# iotchair_uno-shield.net
KiCad netlist of a schematic drawn in EAGLE
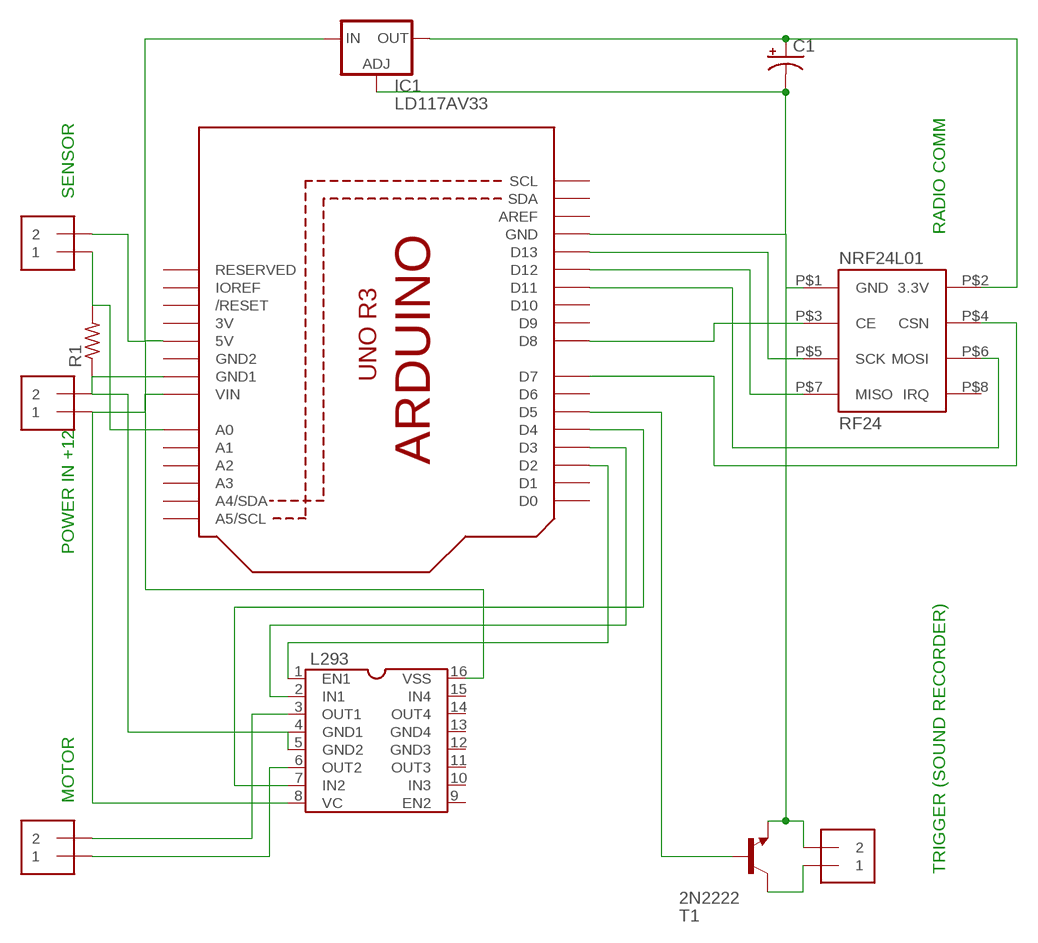
[diagram p0: schematic, sheet 1]

(export (version "E")
  (design (tool "Eeschema 10.0.6"))
  (components
    (comp (ref "+12V")
      (value "1X2-3.5MM")
      (footprint "eagle-import:1X2-3.5MM")
      (libsource (lib "eagle-import") (part "1X2-3.5MM"))
    )
    (comp (ref "A_SENS")
      (value "1X2-3.5MM")
      (footprint "eagle-import:1X2-3.5MM")
      (libsource (lib "eagle-import") (part "1X2-3.5MM"))
    )
    (comp (ref "C1")
      (value "CPOL-USE2-5")
      (footprint "eagle-import:E2-5")
      (libsource (lib "eagle-import") (part "CPOL-USE2-5"))
    )
    (comp (ref "IC1")
      (value "LD117AV33")
      (footprint "eagle-import:TO220L1")
      (libsource (lib "eagle-import") (part "LD117A?V33"))
    )
    (comp (ref "L293")
      (value "DIL16")
      (footprint "eagle-import:DIL16")
      (libsource (lib "eagle-import") (part "DIL16"))
    )
    (comp (ref "MOTOR")
      (value "1X2-3.5MM")
      (footprint "eagle-import:1X2-3.5MM")
      (libsource (lib "eagle-import") (part "1X2-3.5MM"))
    )
    (comp (ref "NRF24L01")
      (value "RF24")
      (footprint "eagle-import:4X2HEADER")
      (libsource (lib "eagle-import") (part "RF24"))
    )
    (comp (ref "R1")
      (value "R-US_0207/10")
      (footprint "eagle-import:0207_10")
      (libsource (lib "eagle-import") (part "R-US_0207/10"))
    )
    (comp (ref "T1")
      (value "2N2222")
      (footprint "eagle-import:TO92-EBC-OVAL")
      (libsource (lib "eagle-import") (part "2N2222"))
    )
    (comp (ref "TRIGGER")
      (value "1X2-3.5MM")
      (footprint "eagle-import:1X2-3.5MM")
      (libsource (lib "eagle-import") (part "1X2-3.5MM"))
    )
    (comp (ref "U1")
      (value "ARDUINOR3-DIMENSION")
      (footprint "eagle-import:ARDUINOR3")
      (libsource (lib "eagle-import") (part "ARDUINOR3-DIMENSION"))
    )
  )
  (nets
    (net (code "1") (name "/3V") (class "Default")
      (node (ref "U1") (pin "3V") (pinfunction "3V_3V") (pintype "power_in"))
    )
    (net (code "2") (name "/GND2") (class "Default")
      (node (ref "U1") (pin "GND2") (pinfunction "GND2_GND2") (pintype "power_in"))
    )
    (net (code "3") (name "Net-(A_SENS-Pad1)") (class "Default")
      (node (ref "A_SENS") (pin "1") (pinfunction "1_1") (pintype "passive"))
      (node (ref "R1") (pin "2") (pinfunction "2_2") (pintype "passive"))
      (node (ref "U1") (pin "A0") (pinfunction "A0_A0") (pintype "bidirectional"))
    )
    (net (code "4") (name "Net-(IC1-ADJ)") (class "Default")
      (node (ref "C1") (pin "-") (pinfunction "-_-") (pintype "passive"))
      (node (ref "IC1") (pin "1") (pinfunction "ADJ_1") (pintype "input"))
      (node (ref "NRF24L01") (pin "P$1") (pinfunction "GND_P$1") (pintype "bidirectional"))
      (node (ref "T1") (pin "E") (pinfunction "E_E") (pintype "passive"))
      (node (ref "TRIGGER") (pin "2") (pinfunction "2_2") (pintype "passive"))
      (node (ref "U1") (pin "GND") (pinfunction "GND_GND") (pintype "power_in"))
    )
    (net (code "5") (name "Net-(IC1-IN)") (class "Default")
      (node (ref "A_SENS") (pin "2") (pinfunction "2_2") (pintype "passive"))
      (node (ref "IC1") (pin "3") (pinfunction "IN_3") (pintype "input"))
      (node (ref "L293") (pin "16") (pinfunction "VSS_16") (pintype "passive"))
      (node (ref "U1") (pin "5V") (pinfunction "5V_5V") (pintype "power_in"))
    )
    (net (code "6") (name "Net-(IC1-OUT)") (class "Default")
      (node (ref "C1") (pin "+") (pinfunction "+_+") (pintype "passive"))
      (node (ref "IC1") (pin "2") (pinfunction "OUT_2") (pintype "passive"))
      (node (ref "NRF24L01") (pin "P$2") (pinfunction "3.3V_P$2") (pintype "bidirectional"))
    )
    (net (code "7") (name "Net-(L293-EN1)") (class "Default")
      (node (ref "L293") (pin "1") (pinfunction "EN1_1") (pintype "passive"))
      (node (ref "U1") (pin "D2") (pinfunction "D2_D2") (pintype "bidirectional"))
    )
    (net (code "8") (name "Net-(L293-GND1)") (class "Default")
      (node (ref "+12V") (pin "2") (pinfunction "2_2") (pintype "passive"))
      (node (ref "L293") (pin "4") (pinfunction "GND1_4") (pintype "passive"))
      (node (ref "L293") (pin "5") (pinfunction "GND2_5") (pintype "passive"))
      (node (ref "R1") (pin "1") (pinfunction "1_1") (pintype "passive"))
      (node (ref "U1") (pin "GND1") (pinfunction "GND1_GND1") (pintype "power_in"))
    )
    (net (code "9") (name "Net-(L293-IN1)") (class "Default")
      (node (ref "L293") (pin "2") (pinfunction "IN1_2") (pintype "passive"))
      (node (ref "U1") (pin "D3") (pinfunction "D3_D3") (pintype "bidirectional"))
    )
    (net (code "10") (name "Net-(L293-IN2)") (class "Default")
      (node (ref "L293") (pin "7") (pinfunction "IN2_7") (pintype "passive"))
      (node (ref "U1") (pin "D4") (pinfunction "D4_D4") (pintype "bidirectional"))
    )
    (net (code "11") (name "Net-(L293-OUT1)") (class "Default")
      (node (ref "L293") (pin "3") (pinfunction "OUT1_3") (pintype "passive"))
      (node (ref "MOTOR") (pin "2") (pinfunction "2_2") (pintype "passive"))
    )
    (net (code "12") (name "Net-(L293-OUT2)") (class "Default")
      (node (ref "L293") (pin "6") (pinfunction "OUT2_6") (pintype "passive"))
      (node (ref "MOTOR") (pin "1") (pinfunction "1_1") (pintype "passive"))
    )
    (net (code "13") (name "Net-(L293-VC)") (class "Default")
      (node (ref "+12V") (pin "1") (pinfunction "1_1") (pintype "passive"))
      (node (ref "L293") (pin "8") (pinfunction "VC_8") (pintype "passive"))
      (node (ref "U1") (pin "VIN") (pinfunction "VIN_VIN") (pintype "power_in"))
    )
    (net (code "14") (name "Net-(NRF24L01-CE)") (class "Default")
      (node (ref "NRF24L01") (pin "P$3") (pinfunction "CE_P$3") (pintype "bidirectional"))
      (node (ref "U1") (pin "D8") (pinfunction "D8_D8") (pintype "bidirectional"))
    )
    (net (code "15") (name "Net-(NRF24L01-CSN)") (class "Default")
      (node (ref "NRF24L01") (pin "P$4") (pinfunction "CSN_P$4") (pintype "bidirectional"))
      (node (ref "U1") (pin "D7") (pinfunction "D7_D7") (pintype "bidirectional"))
    )
    (net (code "16") (name "Net-(NRF24L01-MISO)") (class "Default")
      (node (ref "NRF24L01") (pin "P$7") (pinfunction "MISO_P$7") (pintype "bidirectional"))
      (node (ref "U1") (pin "D12") (pinfunction "D12_D12") (pintype "bidirectional"))
    )
    (net (code "17") (name "Net-(NRF24L01-MOSI)") (class "Default")
      (node (ref "NRF24L01") (pin "P$6") (pinfunction "MOSI_P$6") (pintype "bidirectional"))
      (node (ref "U1") (pin "D11") (pinfunction "D11_D11") (pintype "bidirectional"))
    )
    (net (code "18") (name "Net-(NRF24L01-SCK)") (class "Default")
      (node (ref "NRF24L01") (pin "P$5") (pinfunction "SCK_P$5") (pintype "bidirectional"))
      (node (ref "U1") (pin "D13") (pinfunction "D13_D13") (pintype "bidirectional"))
    )
    (net (code "19") (name "Net-(T1-PadB)") (class "Default")
      (node (ref "T1") (pin "B") (pinfunction "B_B") (pintype "passive"))
      (node (ref "U1") (pin "D5") (pinfunction "D5_D5") (pintype "bidirectional"))
    )
    (net (code "20") (name "Net-(T1-PadC)") (class "Default")
      (node (ref "T1") (pin "C") (pinfunction "C_C") (pintype "passive"))
      (node (ref "TRIGGER") (pin "1") (pinfunction "1_1") (pintype "passive"))
    )
    (net (code "21") (name "unconnected-(L293-EN2-Pad9)") (class "Default")
      (node (ref "L293") (pin "9") (pinfunction "EN2_9") (pintype "passive"))
    )
    (net (code "22") (name "unconnected-(L293-GND3-Pad12)") (class "Default")
      (node (ref "L293") (pin "12") (pinfunction "GND3_12") (pintype "passive"))
    )
    (net (code "23") (name "unconnected-(L293-GND4-Pad13)") (class "Default")
      (node (ref "L293") (pin "13") (pinfunction "GND4_13") (pintype "passive"))
    )
    (net (code "24") (name "unconnected-(L293-IN3-Pad10)") (class "Default")
      (node (ref "L293") (pin "10") (pinfunction "IN3_10") (pintype "passive"))
    )
    (net (code "25") (name "unconnected-(L293-IN4-Pad15)") (class "Default")
      (node (ref "L293") (pin "15") (pinfunction "IN4_15") (pintype "passive"))
    )
    (net (code "26") (name "unconnected-(L293-OUT3-Pad11)") (class "Default")
      (node (ref "L293") (pin "11") (pinfunction "OUT3_11") (pintype "passive"))
    )
    (net (code "27") (name "unconnected-(L293-OUT4-Pad14)") (class "Default")
      (node (ref "L293") (pin "14") (pinfunction "OUT4_14") (pintype "passive"))
    )
    (net (code "28") (name "unconnected-(NRF24L01-IRQ-PadP$8)") (class "Default")
      (node (ref "NRF24L01") (pin "P$8") (pinfunction "IRQ_P$8") (pintype "bidirectional"))
    )
    (net (code "29") (name "unconnected-(U1-A4{slash}SDA-PadA4)") (class "Default")
      (node (ref "U1") (pin "A4") (pinfunction "A4/SDA_A4") (pintype "bidirectional"))
    )
    (net (code "30") (name "unconnected-(U1-A5{slash}SCL-PadA5)") (class "Default")
      (node (ref "U1") (pin "A5") (pinfunction "A5/SCL_A5") (pintype "bidirectional"))
    )
    (net (code "31") (name "unconnected-(U1-PadA1)") (class "Default")
      (node (ref "U1") (pin "A1") (pinfunction "A1_A1") (pintype "bidirectional"))
    )
    (net (code "32") (name "unconnected-(U1-PadA2)") (class "Default")
      (node (ref "U1") (pin "A2") (pinfunction "A2_A2") (pintype "bidirectional"))
    )
    (net (code "33") (name "unconnected-(U1-PadA3)") (class "Default")
      (node (ref "U1") (pin "A3") (pinfunction "A3_A3") (pintype "bidirectional"))
    )
    (net (code "34") (name "unconnected-(U1-PadAREF)") (class "Default")
      (node (ref "U1") (pin "AREF") (pinfunction "AREF_AREF") (pintype "bidirectional"))
    )
    (net (code "35") (name "unconnected-(U1-PadD0)") (class "Default")
      (node (ref "U1") (pin "D0") (pinfunction "D0_D0") (pintype "bidirectional"))
    )
    (net (code "36") (name "unconnected-(U1-PadD1)") (class "Default")
      (node (ref "U1") (pin "D1") (pinfunction "D1_D1") (pintype "bidirectional"))
    )
    (net (code "37") (name "unconnected-(U1-PadD6)") (class "Default")
      (node (ref "U1") (pin "D6") (pinfunction "D6_D6") (pintype "bidirectional"))
    )
    (net (code "38") (name "unconnected-(U1-PadD9)") (class "Default")
      (node (ref "U1") (pin "D9") (pinfunction "D9_D9") (pintype "bidirectional"))
    )
    (net (code "39") (name "unconnected-(U1-PadD10)") (class "Default")
      (node (ref "U1") (pin "D10") (pinfunction "D10_D10") (pintype "bidirectional"))
    )
    (net (code "40") (name "unconnected-(U1-PadIOREF)") (class "Default")
      (node (ref "U1") (pin "IOREF") (pinfunction "IOREF_IOREF") (pintype "output"))
    )
    (net (code "41") (name "unconnected-(U1-PadRESERVED)") (class "Default")
      (node (ref "U1") (pin "RESERVED") (pinfunction "RESERVED_RESERVED") (pintype "no_connect"))
    )
    (net (code "42") (name "unconnected-(U1-PadSCL)") (class "Default")
      (node (ref "U1") (pin "SCL") (pinfunction "SCL_SCL") (pintype "bidirectional"))
    )
    (net (code "43") (name "unconnected-(U1-PadSDA)") (class "Default")
      (node (ref "U1") (pin "SDA") (pinfunction "SDA_SDA") (pintype "bidirectional"))
    )
    (net (code "44") (name "unconnected-(U1-{slash}RESET-PadRESET)") (class "Default")
      (node (ref "U1") (pin "RESET") (pinfunction "/RESET_RESET") (pintype "bidirectional"))
    )
  )
)
